# 1_1.net
KiCad netlist of a schematic drawn in EAGLE
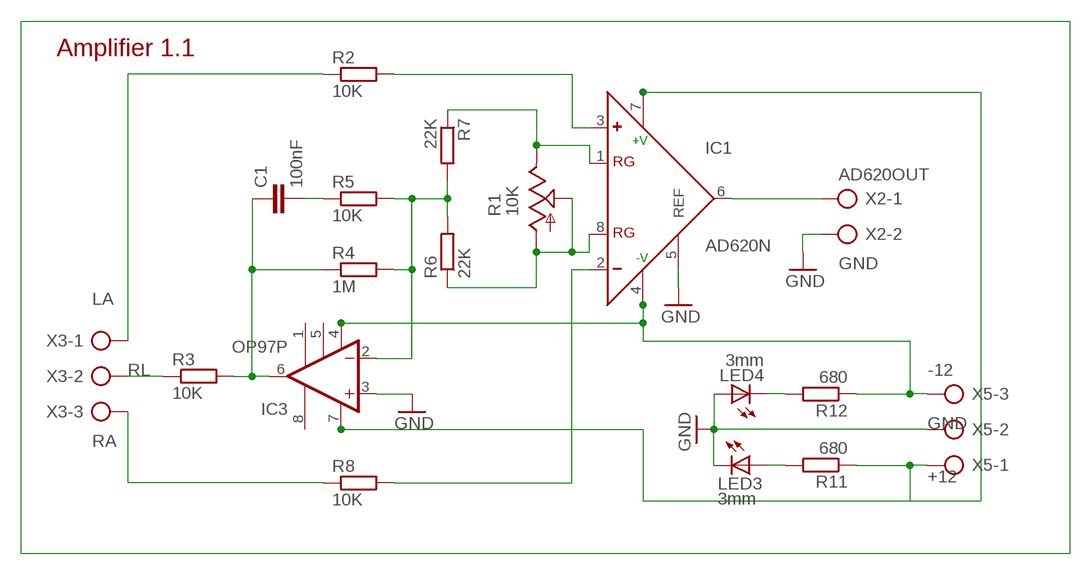
[diagram p0: schematic, sheet 1]

(export (version "E")
  (design (tool "Eeschema 10.0.6"))
  (components
    (comp (ref "C1")
      (value "100nF")
      (footprint "eagle-import:C050-025X075")
      (libsource (lib "eagle-import") (part "C-EU050-025X075"))
    )
    (comp (ref "IC1")
      (value "AD620N")
      (footprint "eagle-import:DIL08")
      (fields (field (name "MF") "ALTERA CORPORATION") (field (name "MPN") "AD620AN"))
      (libsource (lib "eagle-import") (part "AD620N"))
    )
    (comp (ref "IC3")
      (value "OP97P")
      (footprint "eagle-import:DIL08")
      (libsource (lib "eagle-import") (part "OP97P"))
    )
    (comp (ref "LED3")
      (value "3mm")
      (footprint "eagle-import:LED5MM")
      (libsource (lib "eagle-import") (part "LED5MM"))
    )
    (comp (ref "LED4")
      (value "3mm")
      (footprint "eagle-import:LED5MM")
      (libsource (lib "eagle-import") (part "LED5MM"))
    )
    (comp (ref "R1")
      (value "10K")
      (footprint "eagle-import:RJ9W")
      (libsource (lib "eagle-import") (part "TRIM_US-RJ9W"))
    )
    (comp (ref "R2")
      (value "10K")
      (footprint "eagle-import:0207_10")
      (libsource (lib "eagle-import") (part "R-EU_0207/10"))
    )
    (comp (ref "R3")
      (value "10K")
      (footprint "eagle-import:0207_10")
      (libsource (lib "eagle-import") (part "R-EU_0207/10"))
    )
    (comp (ref "R4")
      (value "1M")
      (footprint "eagle-import:0207_10")
      (libsource (lib "eagle-import") (part "R-EU_0207/10"))
    )
    (comp (ref "R5")
      (value "10K")
      (footprint "eagle-import:0207_10")
      (libsource (lib "eagle-import") (part "R-EU_0207/10"))
    )
    (comp (ref "R6")
      (value "22K")
      (footprint "eagle-import:0207_10")
      (libsource (lib "eagle-import") (part "R-EU_0207/10"))
    )
    (comp (ref "R7")
      (value "22K")
      (footprint "eagle-import:0207_10")
      (libsource (lib "eagle-import") (part "R-EU_0207/10"))
    )
    (comp (ref "R8")
      (value "10K")
      (footprint "eagle-import:0207_10")
      (libsource (lib "eagle-import") (part "R-EU_0207/10"))
    )
    (comp (ref "R11")
      (value "680")
      (footprint "eagle-import:0207_10")
      (libsource (lib "eagle-import") (part "R-EU_0207/10"))
    )
    (comp (ref "R12")
      (value "680")
      (footprint "eagle-import:0207_10")
      (libsource (lib "eagle-import") (part "R-EU_0207/10"))
    )
    (comp (ref "X2")
      (value "AK500/2-H")
      (footprint "eagle-import:AK500_2-H")
      (libsource (lib "eagle-import") (part "AK500/2-H"))
    )
    (comp (ref "X3")
      (value "AK500/3-H")
      (footprint "eagle-import:AK500_3-H")
      (libsource (lib "eagle-import") (part "AK500/3-H"))
    )
    (comp (ref "X5")
      (value "AK500/3-H")
      (footprint "eagle-import:AK500_3-H")
      (libsource (lib "eagle-import") (part "AK500/3-H"))
    )
  )
  (nets
    (net (code "1") (name "/+12") (class "Default")
      (node (ref "IC1") (pin "7") (pinfunction "+V_7") (pintype "power_in"))
      (node (ref "IC3") (pin "7") (pinfunction "V+_7") (pintype "power_in"))
      (node (ref "R11") (pin "1") (pinfunction "1_1") (pintype "passive"))
      (node (ref "X5") (pin "1") (pinfunction "KL_1") (pintype "passive"))
    )
    (net (code "2") (name "/-12") (class "Default")
      (node (ref "IC1") (pin "4") (pinfunction "-V_4") (pintype "power_in"))
      (node (ref "IC3") (pin "4") (pinfunction "V-_4") (pintype "power_in"))
      (node (ref "R12") (pin "1") (pinfunction "1_1") (pintype "passive"))
      (node (ref "X5") (pin "3") (pinfunction "KL_3") (pintype "passive"))
    )
    (net (code "3") (name "/AD620OUT") (class "Default")
      (node (ref "IC1") (pin "6") (pinfunction "OUT_6") (pintype "output"))
      (node (ref "X2") (pin "1") (pinfunction "KL_1") (pintype "passive"))
    )
    (net (code "4") (name "/LA") (class "Default")
      (node (ref "R2") (pin "1") (pinfunction "1_1") (pintype "passive"))
      (node (ref "X3") (pin "1") (pinfunction "KL_1") (pintype "passive"))
    )
    (net (code "5") (name "/RA") (class "Default")
      (node (ref "R8") (pin "1") (pinfunction "1_1") (pintype "passive"))
      (node (ref "X3") (pin "3") (pinfunction "KL_3") (pintype "passive"))
    )
    (net (code "6") (name "/RL") (class "Default")
      (node (ref "R3") (pin "1") (pinfunction "1_1") (pintype "passive"))
      (node (ref "X3") (pin "2") (pinfunction "KL_2") (pintype "passive"))
    )
    (net (code "7") (name "GND") (class "Default")
      (node (ref "IC1") (pin "5") (pinfunction "REF_5") (pintype "passive"))
      (node (ref "IC3") (pin "3") (pinfunction "+IN_3") (pintype "input"))
      (node (ref "LED3") (pin "K") (pinfunction "C_K") (pintype "passive"))
      (node (ref "LED4") (pin "A") (pinfunction "A_A") (pintype "passive"))
      (node (ref "X2") (pin "2") (pinfunction "KL_2") (pintype "passive"))
      (node (ref "X5") (pin "2") (pinfunction "KL_2") (pintype "passive"))
    )
    (net (code "8") (name "Net-(C1-Pad2)") (class "Default")
      (node (ref "C1") (pin "2") (pinfunction "2_2") (pintype "passive"))
      (node (ref "R5") (pin "1") (pinfunction "1_1") (pintype "passive"))
    )
    (net (code "9") (name "Net-(IC1-+)") (class "Default")
      (node (ref "IC1") (pin "3") (pinfunction "+_3") (pintype "input"))
      (node (ref "R2") (pin "2") (pinfunction "2_2") (pintype "passive"))
    )
    (net (code "10") (name "Net-(IC1--)") (class "Default")
      (node (ref "IC1") (pin "2") (pinfunction "-_2") (pintype "input"))
      (node (ref "R8") (pin "2") (pinfunction "2_2") (pintype "passive"))
    )
    (net (code "11") (name "Net-(IC1-RG-Pad1)") (class "Default")
      (node (ref "IC1") (pin "1") (pinfunction "RG_1") (pintype "passive"))
      (node (ref "R1") (pin "E") (pinfunction "E_E") (pintype "passive"))
      (node (ref "R7") (pin "1") (pinfunction "1_1") (pintype "passive"))
    )
    (net (code "12") (name "Net-(IC1-RG-Pad8)") (class "Default")
      (node (ref "IC1") (pin "8") (pinfunction "RG_8") (pintype "passive"))
      (node (ref "R1") (pin "A") (pinfunction "A_A") (pintype "passive"))
      (node (ref "R1") (pin "S") (pinfunction "S_S") (pintype "passive"))
      (node (ref "R6") (pin "1") (pinfunction "1_1") (pintype "passive"))
    )
    (net (code "13") (name "Net-(IC3--IN)") (class "Default")
      (node (ref "IC3") (pin "2") (pinfunction "-IN_2") (pintype "input"))
      (node (ref "R4") (pin "2") (pinfunction "2_2") (pintype "passive"))
      (node (ref "R5") (pin "2") (pinfunction "2_2") (pintype "passive"))
      (node (ref "R6") (pin "2") (pinfunction "2_2") (pintype "passive"))
      (node (ref "R7") (pin "2") (pinfunction "2_2") (pintype "passive"))
    )
    (net (code "14") (name "Net-(IC3-OUT)") (class "Default")
      (node (ref "C1") (pin "1") (pinfunction "1_1") (pintype "passive"))
      (node (ref "IC3") (pin "6") (pinfunction "OUT_6") (pintype "output"))
      (node (ref "R3") (pin "2") (pinfunction "2_2") (pintype "passive"))
      (node (ref "R4") (pin "1") (pinfunction "1_1") (pintype "passive"))
    )
    (net (code "15") (name "Net-(LED3-PadA)") (class "Default")
      (node (ref "LED3") (pin "A") (pinfunction "A_A") (pintype "passive"))
      (node (ref "R11") (pin "2") (pinfunction "2_2") (pintype "passive"))
    )
    (net (code "16") (name "Net-(LED4-C)") (class "Default")
      (node (ref "LED4") (pin "K") (pinfunction "C_K") (pintype "passive"))
      (node (ref "R12") (pin "2") (pinfunction "2_2") (pintype "passive"))
    )
    (net (code "17") (name "unconnected-(IC3-BAL1-Pad1)") (class "Default")
      (node (ref "IC3") (pin "1") (pinfunction "BAL1_1") (pintype "passive"))
    )
    (net (code "18") (name "unconnected-(IC3-BAL2-Pad8)") (class "Default")
      (node (ref "IC3") (pin "8") (pinfunction "BAL2_8") (pintype "passive"))
    )
    (net (code "19") (name "unconnected-(IC3-COMP-Pad5)") (class "Default")
      (node (ref "IC3") (pin "5") (pinfunction "COMP_5") (pintype "passive"))
    )
  )
)
